# USBSerial.net
KiCad netlist of a schematic drawn in EAGLE
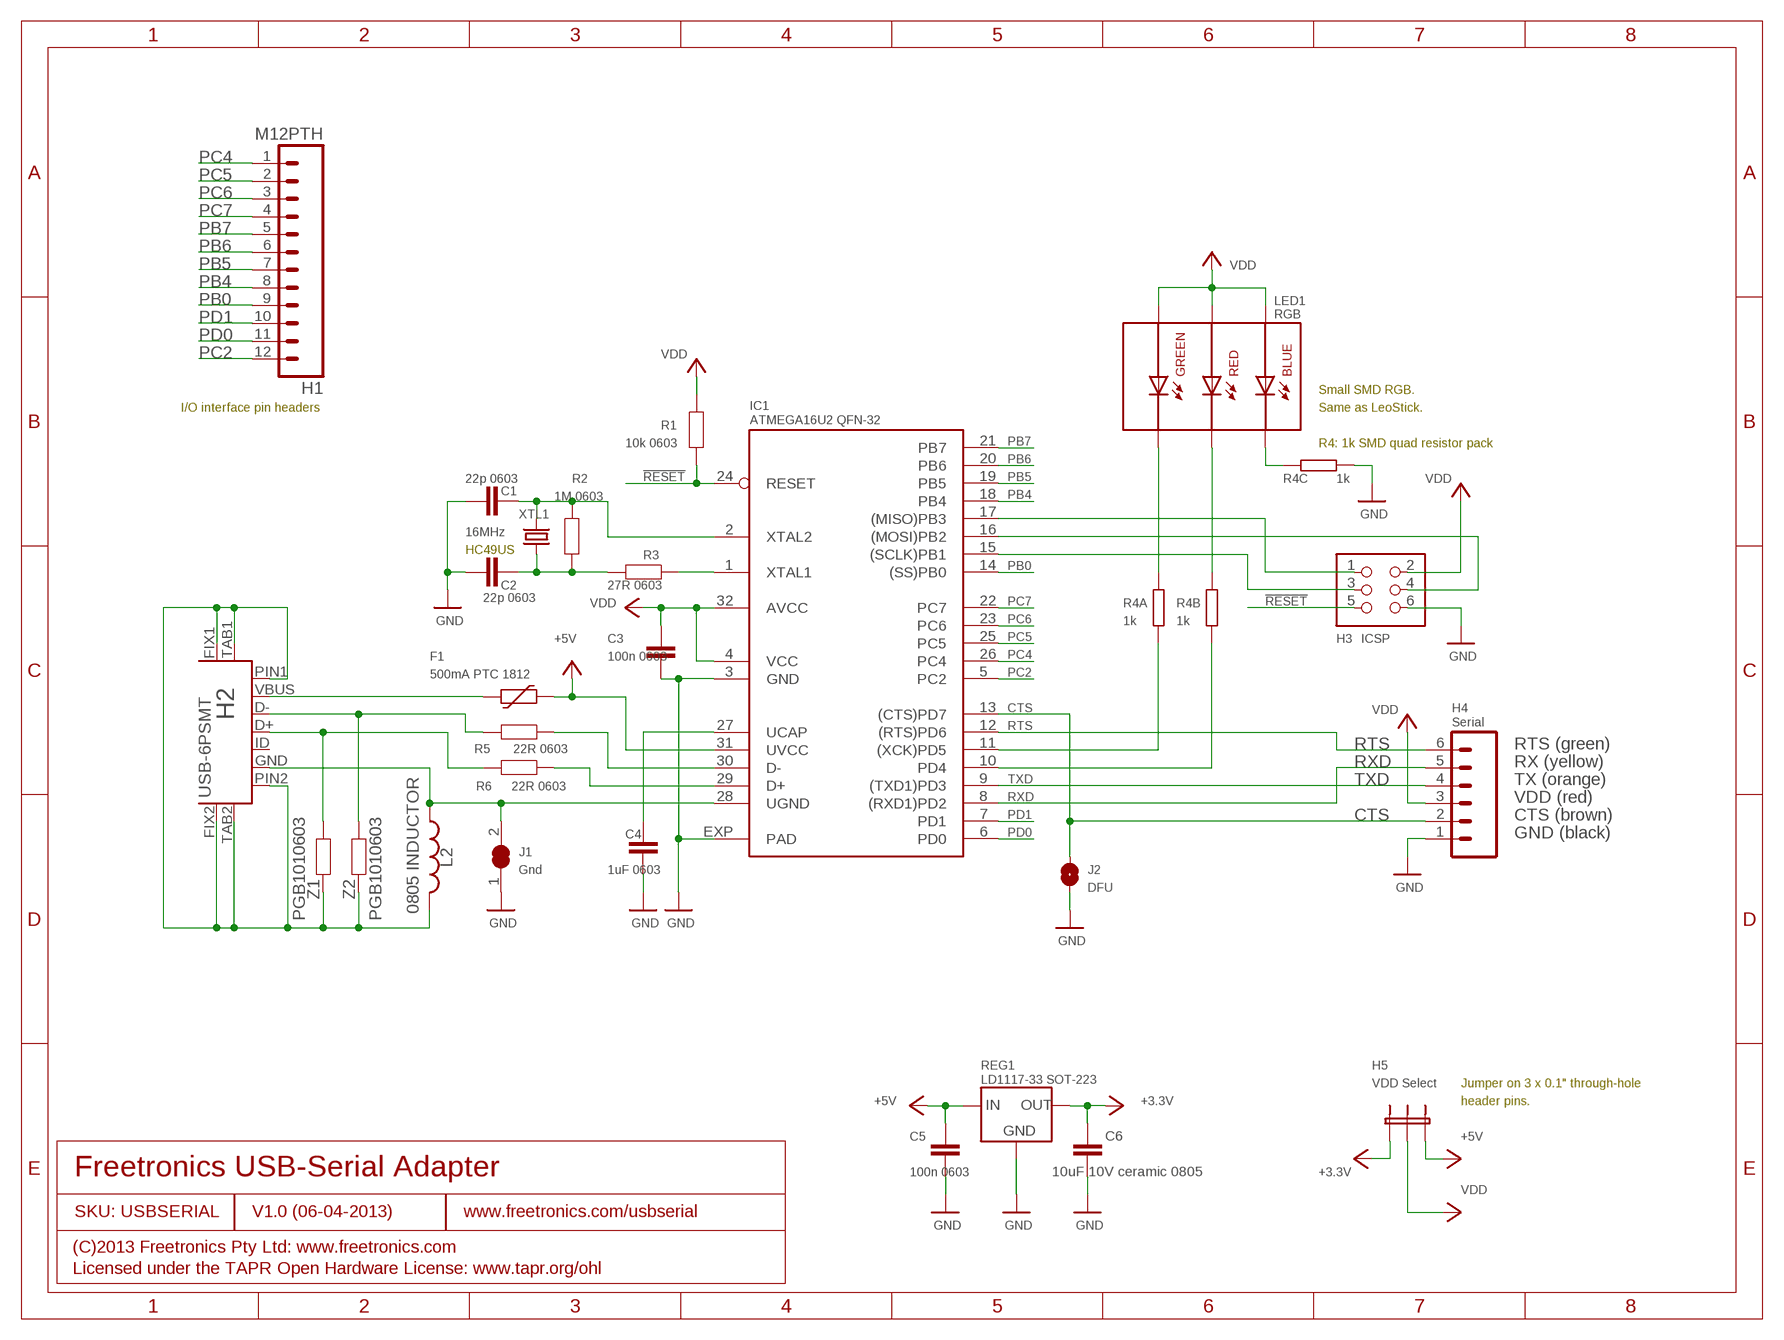
[diagram p0: schematic, sheet 1]

(export (version "E")
  (design (tool "Eeschema 10.0.6"))
  (components
    (comp (ref "C1")
      (value "22p 0603")
      (footprint "eagle-import:0603")
      (libsource (lib "eagle-import") (part "CAP0603"))
    )
    (comp (ref "C2")
      (value "22p 0603")
      (footprint "eagle-import:0603")
      (libsource (lib "eagle-import") (part "CAP0603"))
    )
    (comp (ref "C3")
      (value "100n 0603")
      (footprint "eagle-import:0603")
      (libsource (lib "eagle-import") (part "CAP0603"))
    )
    (comp (ref "C4")
      (value "1uF 0603")
      (footprint "eagle-import:0603")
      (libsource (lib "eagle-import") (part "CAP0603"))
    )
    (comp (ref "C5")
      (value "100n 0603")
      (footprint "eagle-import:0603")
      (libsource (lib "eagle-import") (part "CAP0603"))
    )
    (comp (ref "C6")
      (value "10uF 10V ceramic 0805")
      (footprint "eagle-import:C0805")
      (libsource (lib "eagle-import") (part "C-EUC0805"))
    )
    (comp (ref "F1")
      (value "500mA PTC 1812")
      (footprint "eagle-import:1812")
      (libsource (lib "eagle-import") (part "PTC"))
    )
    (comp (ref "H1")
      (value "M12PTH")
      (footprint "eagle-import:1X12")
      (libsource (lib "eagle-import") (part "M12PTH"))
    )
    (comp (ref "H2")
      (value "USB-6PSMT")
      (footprint "eagle-import:USB-MICROB-MB05PMXX")
      (libsource (lib "eagle-import") (part "USB-6PSMT"))
    )
    (comp (ref "H3")
      (value "ICSP")
      (footprint "eagle-import:HEADER_2X3")
      (libsource (lib "eagle-import") (part "HEADER_2X3"))
    )
    (comp (ref "H4")
      (value "Serial")
      (footprint "eagle-import:1X06")
      (libsource (lib "eagle-import") (part "M06SIP"))
    )
    (comp (ref "H5")
      (value "VDD Select")
      (footprint "eagle-import:JUMPER_SPDT")
      (libsource (lib "eagle-import") (part "JUMPER_SPDT"))
    )
    (comp (ref "IC1")
      (value "ATMEGA16U2 QFN-32")
      (footprint "eagle-import:ATMEL_QFN32")
      (libsource (lib "eagle-import") (part "ATMEL_ATMEGA8U2-MUQFN"))
    )
    (comp (ref "J1")
      (value "Gnd")
      (footprint "eagle-import:SJC")
      (libsource (lib "eagle-import") (part "SJCN"))
    )
    (comp (ref "J2") (value "DFU") (footprint "eagle-import:SJ") (libsource (lib "eagle-import") (part "SJ")))
    (comp (ref "L2")
      (value "0805 INDUCTOR")
      (footprint "eagle-import:0805-LARGE")
      (libsource (lib "eagle-import") (part "INDUCTOR0805-LARGE"))
    )
    (comp (ref "LED1")
      (value "RGB")
      (footprint "eagle-import:19-337")
      (libsource (lib "eagle-import") (part "RGBLEDSMT"))
    )
    (comp (ref "R1")
      (value "10k 0603")
      (footprint "eagle-import:0603")
      (libsource (lib "eagle-import") (part "RESISTOR0603"))
    )
    (comp (ref "R2")
      (value "1M 0603")
      (footprint "eagle-import:0603")
      (libsource (lib "eagle-import") (part "RESISTOR0603"))
    )
    (comp (ref "R3")
      (value "27R 0603")
      (footprint "eagle-import:0603")
      (libsource (lib "eagle-import") (part "RESISTOR0603"))
    )
    (comp (ref "R4")
      (value "1k")
      (footprint "eagle-import:CAY16")
      (libsource (lib "eagle-import") (part "CAY16"))
    )
    (comp (ref "R5")
      (value "22R 0603")
      (footprint "eagle-import:0603")
      (libsource (lib "eagle-import") (part "RESISTOR0603"))
    )
    (comp (ref "R6")
      (value "22R 0603")
      (footprint "eagle-import:0603")
      (libsource (lib "eagle-import") (part "RESISTOR0603"))
    )
    (comp (ref "REG1")
      (value "LD1117-33 SOT-223")
      (footprint "eagle-import:SOT-223")
      (libsource (lib "eagle-import") (part "LD1117-FIXED"))
    )
    (comp (ref "XTL1")
      (value "16MHz")
      (footprint "eagle-import:HC49US")
      (libsource (lib "eagle-import") (part "CRYSTALHC49US"))
    )
    (comp (ref "Z1")
      (value "PGB1010603")
      (footprint "eagle-import:0603")
      (libsource (lib "eagle-import") (part "RESISTOR0603"))
    )
    (comp (ref "Z2")
      (value "PGB1010603")
      (footprint "eagle-import:0603")
      (libsource (lib "eagle-import") (part "RESISTOR0603"))
    )
  )
  (nets
    (net (code "1") (name "+3.3V") (class "Default")
      (node (ref "C6") (pin "1") (pinfunction "1_1") (pintype "passive"))
      (node (ref "H5") (pin "1") (pinfunction "1_1") (pintype "passive"))
      (node (ref "REG1") (pin "2") (pinfunction "OUT_2") (pintype "power_in"))
      (node (ref "REG1") (pin "4") (pinfunction "OUT_4") (pintype "power_in"))
    )
    (net (code "2") (name "+5V") (class "Default")
      (node (ref "C5") (pin "1") (pinfunction "1_1") (pintype "passive"))
      (node (ref "F1") (pin "2") (pinfunction "P$2_2") (pintype "bidirectional"))
      (node (ref "H5") (pin "3") (pinfunction "3_3") (pintype "passive"))
      (node (ref "IC1") (pin "31") (pinfunction "UVCC_31") (pintype "power_in"))
      (node (ref "REG1") (pin "3") (pinfunction "IN_3") (pintype "input"))
    )
    (net (code "3") (name "/CTS") (class "Default")
      (node (ref "H4") (pin "2") (pinfunction "2_2") (pintype "passive"))
      (node (ref "IC1") (pin "13") (pinfunction "(CTS)PD7_13") (pintype "bidirectional"))
      (node (ref "J2") (pin "2") (pinfunction "2_2") (pintype "passive"))
    )
    (net (code "4") (name "/PB0") (class "Default")
      (node (ref "H1") (pin "9") (pinfunction "9_9") (pintype "passive"))
      (node (ref "IC1") (pin "14") (pinfunction "(SS)PB0_14") (pintype "bidirectional"))
    )
    (net (code "5") (name "/PB4") (class "Default")
      (node (ref "H1") (pin "8") (pinfunction "8_8") (pintype "passive"))
      (node (ref "IC1") (pin "18") (pinfunction "PB4_18") (pintype "bidirectional"))
    )
    (net (code "6") (name "/PB5") (class "Default")
      (node (ref "H1") (pin "7") (pinfunction "7_7") (pintype "passive"))
      (node (ref "IC1") (pin "19") (pinfunction "PB5_19") (pintype "bidirectional"))
    )
    (net (code "7") (name "/PB6") (class "Default")
      (node (ref "H1") (pin "6") (pinfunction "6_6") (pintype "passive"))
      (node (ref "IC1") (pin "20") (pinfunction "PB6_20") (pintype "bidirectional"))
    )
    (net (code "8") (name "/PB7") (class "Default")
      (node (ref "H1") (pin "5") (pinfunction "5_5") (pintype "passive"))
      (node (ref "IC1") (pin "21") (pinfunction "PB7_21") (pintype "bidirectional"))
    )
    (net (code "9") (name "/PC2") (class "Default")
      (node (ref "H1") (pin "12") (pinfunction "12_12") (pintype "passive"))
      (node (ref "IC1") (pin "5") (pinfunction "PC2_5") (pintype "bidirectional"))
    )
    (net (code "10") (name "/PC4") (class "Default")
      (node (ref "H1") (pin "1") (pinfunction "1_1") (pintype "passive"))
      (node (ref "IC1") (pin "26") (pinfunction "PC4_26") (pintype "bidirectional"))
    )
    (net (code "11") (name "/PC5") (class "Default")
      (node (ref "H1") (pin "2") (pinfunction "2_2") (pintype "passive"))
      (node (ref "IC1") (pin "25") (pinfunction "PC5_25") (pintype "bidirectional"))
    )
    (net (code "12") (name "/PC6") (class "Default")
      (node (ref "H1") (pin "3") (pinfunction "3_3") (pintype "passive"))
      (node (ref "IC1") (pin "23") (pinfunction "PC6_23") (pintype "bidirectional"))
    )
    (net (code "13") (name "/PC7") (class "Default")
      (node (ref "H1") (pin "4") (pinfunction "4_4") (pintype "passive"))
      (node (ref "IC1") (pin "22") (pinfunction "PC7_22") (pintype "bidirectional"))
    )
    (net (code "14") (name "/PD0") (class "Default")
      (node (ref "H1") (pin "11") (pinfunction "11_11") (pintype "passive"))
      (node (ref "IC1") (pin "6") (pinfunction "PD0_6") (pintype "bidirectional"))
    )
    (net (code "15") (name "/PD1") (class "Default")
      (node (ref "H1") (pin "10") (pinfunction "10_10") (pintype "passive"))
      (node (ref "IC1") (pin "7") (pinfunction "PD1_7") (pintype "bidirectional"))
    )
    (net (code "16") (name "/RTS") (class "Default")
      (node (ref "H4") (pin "6") (pinfunction "6_6") (pintype "passive"))
      (node (ref "IC1") (pin "12") (pinfunction "(RTS)PD6_12") (pintype "bidirectional"))
    )
    (net (code "17") (name "/RXD") (class "Default")
      (node (ref "H4") (pin "5") (pinfunction "5_5") (pintype "passive"))
      (node (ref "IC1") (pin "8") (pinfunction "(RXD1)PD2_8") (pintype "bidirectional"))
    )
    (net (code "18") (name "/TXD") (class "Default")
      (node (ref "H4") (pin "4") (pinfunction "4_4") (pintype "passive"))
      (node (ref "IC1") (pin "9") (pinfunction "(TXD1)PD3_9") (pintype "bidirectional"))
    )
    (net (code "19") (name "/~{RESET}") (class "Default")
      (node (ref "H3") (pin "5") (pinfunction "5_5") (pintype "passive"))
      (node (ref "IC1") (pin "24") (pinfunction "RESET_24") (pintype "input"))
      (node (ref "R1") (pin "1") (pinfunction "1_1") (pintype "passive"))
    )
    (net (code "20") (name "GND") (class "Default")
      (node (ref "C1") (pin "1") (pinfunction "1_1") (pintype "passive"))
      (node (ref "C2") (pin "1") (pinfunction "1_1") (pintype "passive"))
      (node (ref "C3") (pin "2") (pinfunction "2_2") (pintype "passive"))
      (node (ref "C4") (pin "2") (pinfunction "2_2") (pintype "passive"))
      (node (ref "C5") (pin "2") (pinfunction "2_2") (pintype "passive"))
      (node (ref "C6") (pin "2") (pinfunction "2_2") (pintype "passive"))
      (node (ref "H3") (pin "6") (pinfunction "6_6") (pintype "passive"))
      (node (ref "H4") (pin "1") (pinfunction "1_1") (pintype "passive"))
      (node (ref "IC1") (pin "3") (pinfunction "GND_3") (pintype "power_in"))
      (node (ref "IC1") (pin "EXP") (pinfunction "PAD_EXP") (pintype "power_in"))
      (node (ref "J1") (pin "1") (pinfunction "1_1") (pintype "passive"))
      (node (ref "J2") (pin "1") (pinfunction "1_1") (pintype "passive"))
      (node (ref "R4") (pin "6") (pinfunction "2_6") (pintype "passive"))
      (node (ref "REG1") (pin "1") (pinfunction "GND_1") (pintype "input"))
    )
    (net (code "21") (name "Net-(C2-Pad2)") (class "Default")
      (node (ref "C2") (pin "2") (pinfunction "2_2") (pintype "passive"))
      (node (ref "R2") (pin "1") (pinfunction "1_1") (pintype "passive"))
      (node (ref "R3") (pin "2") (pinfunction "2_2") (pintype "passive"))
      (node (ref "XTL1") (pin "1") (pinfunction "1_1") (pintype "passive"))
    )
    (net (code "22") (name "Net-(F1-P$1)") (class "Default")
      (node (ref "F1") (pin "1") (pinfunction "P$1_1") (pintype "bidirectional"))
      (node (ref "H2") (pin "VBUS") (pinfunction "VBUS_VBUS") (pintype "bidirectional"))
    )
    (net (code "23") (name "Net-(H2-PadD+)") (class "Default")
      (node (ref "H2") (pin "D+") (pinfunction "D+_D+") (pintype "bidirectional"))
      (node (ref "R6") (pin "2") (pinfunction "2_2") (pintype "passive"))
      (node (ref "Z1") (pin "1") (pinfunction "1_1") (pintype "passive"))
    )
    (net (code "24") (name "Net-(H2-PadD-)") (class "Default")
      (node (ref "H2") (pin "D-") (pinfunction "D-_D-") (pintype "bidirectional"))
      (node (ref "R5") (pin "2") (pinfunction "2_2") (pintype "passive"))
      (node (ref "Z2") (pin "1") (pinfunction "1_1") (pintype "passive"))
    )
    (net (code "25") (name "Net-(H2-PadFIX1)") (class "Default")
      (node (ref "H2") (pin "FIX1") (pinfunction "FIX1_FIX1") (pintype "bidirectional"))
      (node (ref "H2") (pin "FIX2") (pinfunction "FIX2_FIX2") (pintype "bidirectional"))
      (node (ref "H2") (pin "PIN1") (pinfunction "PIN1_PIN1") (pintype "bidirectional"))
      (node (ref "H2") (pin "PIN2") (pinfunction "PIN2_PIN2") (pintype "bidirectional"))
      (node (ref "H2") (pin "TAB1") (pinfunction "TAB1_TAB1") (pintype "bidirectional"))
      (node (ref "H2") (pin "TAB2") (pinfunction "TAB2_TAB2") (pintype "bidirectional"))
      (node (ref "L2") (pin "2") (pinfunction "2_2") (pintype "passive"))
      (node (ref "Z1") (pin "2") (pinfunction "2_2") (pintype "passive"))
      (node (ref "Z2") (pin "2") (pinfunction "2_2") (pintype "passive"))
    )
    (net (code "26") (name "Net-(IC1-(MISO)PB3)") (class "Default")
      (node (ref "H3") (pin "1") (pinfunction "1_1") (pintype "passive"))
      (node (ref "IC1") (pin "17") (pinfunction "(MISO)PB3_17") (pintype "bidirectional"))
    )
    (net (code "27") (name "Net-(IC1-(MOSI)PB2)") (class "Default")
      (node (ref "H3") (pin "4") (pinfunction "4_4") (pintype "passive"))
      (node (ref "IC1") (pin "16") (pinfunction "(MOSI)PB2_16") (pintype "bidirectional"))
    )
    (net (code "28") (name "Net-(IC1-(SCLK)PB1)") (class "Default")
      (node (ref "H3") (pin "3") (pinfunction "3_3") (pintype "passive"))
      (node (ref "IC1") (pin "15") (pinfunction "(SCLK)PB1_15") (pintype "bidirectional"))
    )
    (net (code "29") (name "Net-(IC1-(XCK)PD5)") (class "Default")
      (node (ref "IC1") (pin "11") (pinfunction "(XCK)PD5_11") (pintype "bidirectional"))
      (node (ref "R4") (pin "8") (pinfunction "2_8") (pintype "passive"))
    )
    (net (code "30") (name "Net-(IC1-D+)") (class "Default")
      (node (ref "IC1") (pin "29") (pinfunction "D+_29") (pintype "bidirectional"))
      (node (ref "R6") (pin "1") (pinfunction "1_1") (pintype "passive"))
    )
    (net (code "31") (name "Net-(IC1-D-)") (class "Default")
      (node (ref "IC1") (pin "30") (pinfunction "D-_30") (pintype "bidirectional"))
      (node (ref "R5") (pin "1") (pinfunction "1_1") (pintype "passive"))
    )
    (net (code "32") (name "Net-(IC1-PD4)") (class "Default")
      (node (ref "IC1") (pin "10") (pinfunction "PD4_10") (pintype "bidirectional"))
      (node (ref "R4") (pin "7") (pinfunction "2_7") (pintype "passive"))
    )
    (net (code "33") (name "Net-(IC1-UCAP)") (class "Default")
      (node (ref "C4") (pin "1") (pinfunction "1_1") (pintype "passive"))
      (node (ref "IC1") (pin "27") (pinfunction "UCAP_27") (pintype "passive"))
    )
    (net (code "34") (name "Net-(IC1-UGND)") (class "Default")
      (node (ref "H2") (pin "GND") (pinfunction "GND_GND") (pintype "bidirectional"))
      (node (ref "IC1") (pin "28") (pinfunction "UGND_28") (pintype "power_in"))
      (node (ref "J1") (pin "2") (pinfunction "2_2") (pintype "passive"))
      (node (ref "L2") (pin "1") (pinfunction "1_1") (pintype "passive"))
    )
    (net (code "35") (name "Net-(IC1-XTAL1)") (class "Default")
      (node (ref "IC1") (pin "1") (pinfunction "XTAL1_1") (pintype "bidirectional"))
      (node (ref "R3") (pin "1") (pinfunction "1_1") (pintype "passive"))
    )
    (net (code "36") (name "Net-(IC1-XTAL2)") (class "Default")
      (node (ref "C1") (pin "2") (pinfunction "2_2") (pintype "passive"))
      (node (ref "IC1") (pin "2") (pinfunction "XTAL2_2") (pintype "bidirectional"))
      (node (ref "R2") (pin "2") (pinfunction "2_2") (pintype "passive"))
      (node (ref "XTL1") (pin "2") (pinfunction "2_2") (pintype "passive"))
    )
    (net (code "37") (name "Net-(LED1-C-B)") (class "Default")
      (node (ref "LED1") (pin "1") (pinfunction "C-B_1") (pintype "passive"))
      (node (ref "R4") (pin "3") (pinfunction "1_3") (pintype "passive"))
    )
    (net (code "38") (name "Net-(LED1-C-G)") (class "Default")
      (node (ref "LED1") (pin "3") (pinfunction "C-G_3") (pintype "passive"))
      (node (ref "R4") (pin "1") (pinfunction "1_1") (pintype "passive"))
    )
    (net (code "39") (name "Net-(LED1-C-R)") (class "Default")
      (node (ref "LED1") (pin "2") (pinfunction "C-R_2") (pintype "passive"))
      (node (ref "R4") (pin "2") (pinfunction "1_2") (pintype "passive"))
    )
    (net (code "40") (name "VDD") (class "Default")
      (node (ref "C3") (pin "1") (pinfunction "1_1") (pintype "passive"))
      (node (ref "H3") (pin "2") (pinfunction "2_2") (pintype "passive"))
      (node (ref "H4") (pin "3") (pinfunction "3_3") (pintype "passive"))
      (node (ref "H5") (pin "2") (pinfunction "2_2") (pintype "passive"))
      (node (ref "IC1") (pin "32") (pinfunction "AVCC_32") (pintype "power_in"))
      (node (ref "IC1") (pin "4") (pinfunction "VCC_4") (pintype "power_in"))
      (node (ref "LED1") (pin "4") (pinfunction "A-B_4") (pintype "passive"))
      (node (ref "LED1") (pin "5") (pinfunction "A-R_5") (pintype "passive"))
      (node (ref "LED1") (pin "6") (pinfunction "A-G_6") (pintype "passive"))
      (node (ref "R1") (pin "2") (pinfunction "2_2") (pintype "passive"))
    )
    (net (code "41") (name "unconnected-(H2-PadID)") (class "Default")
      (node (ref "H2") (pin "ID") (pinfunction "ID_ID") (pintype "bidirectional"))
    )
  )
)
